# Server_DDR3L.net
KiCad netlist of a schematic drawn in Altium Designer
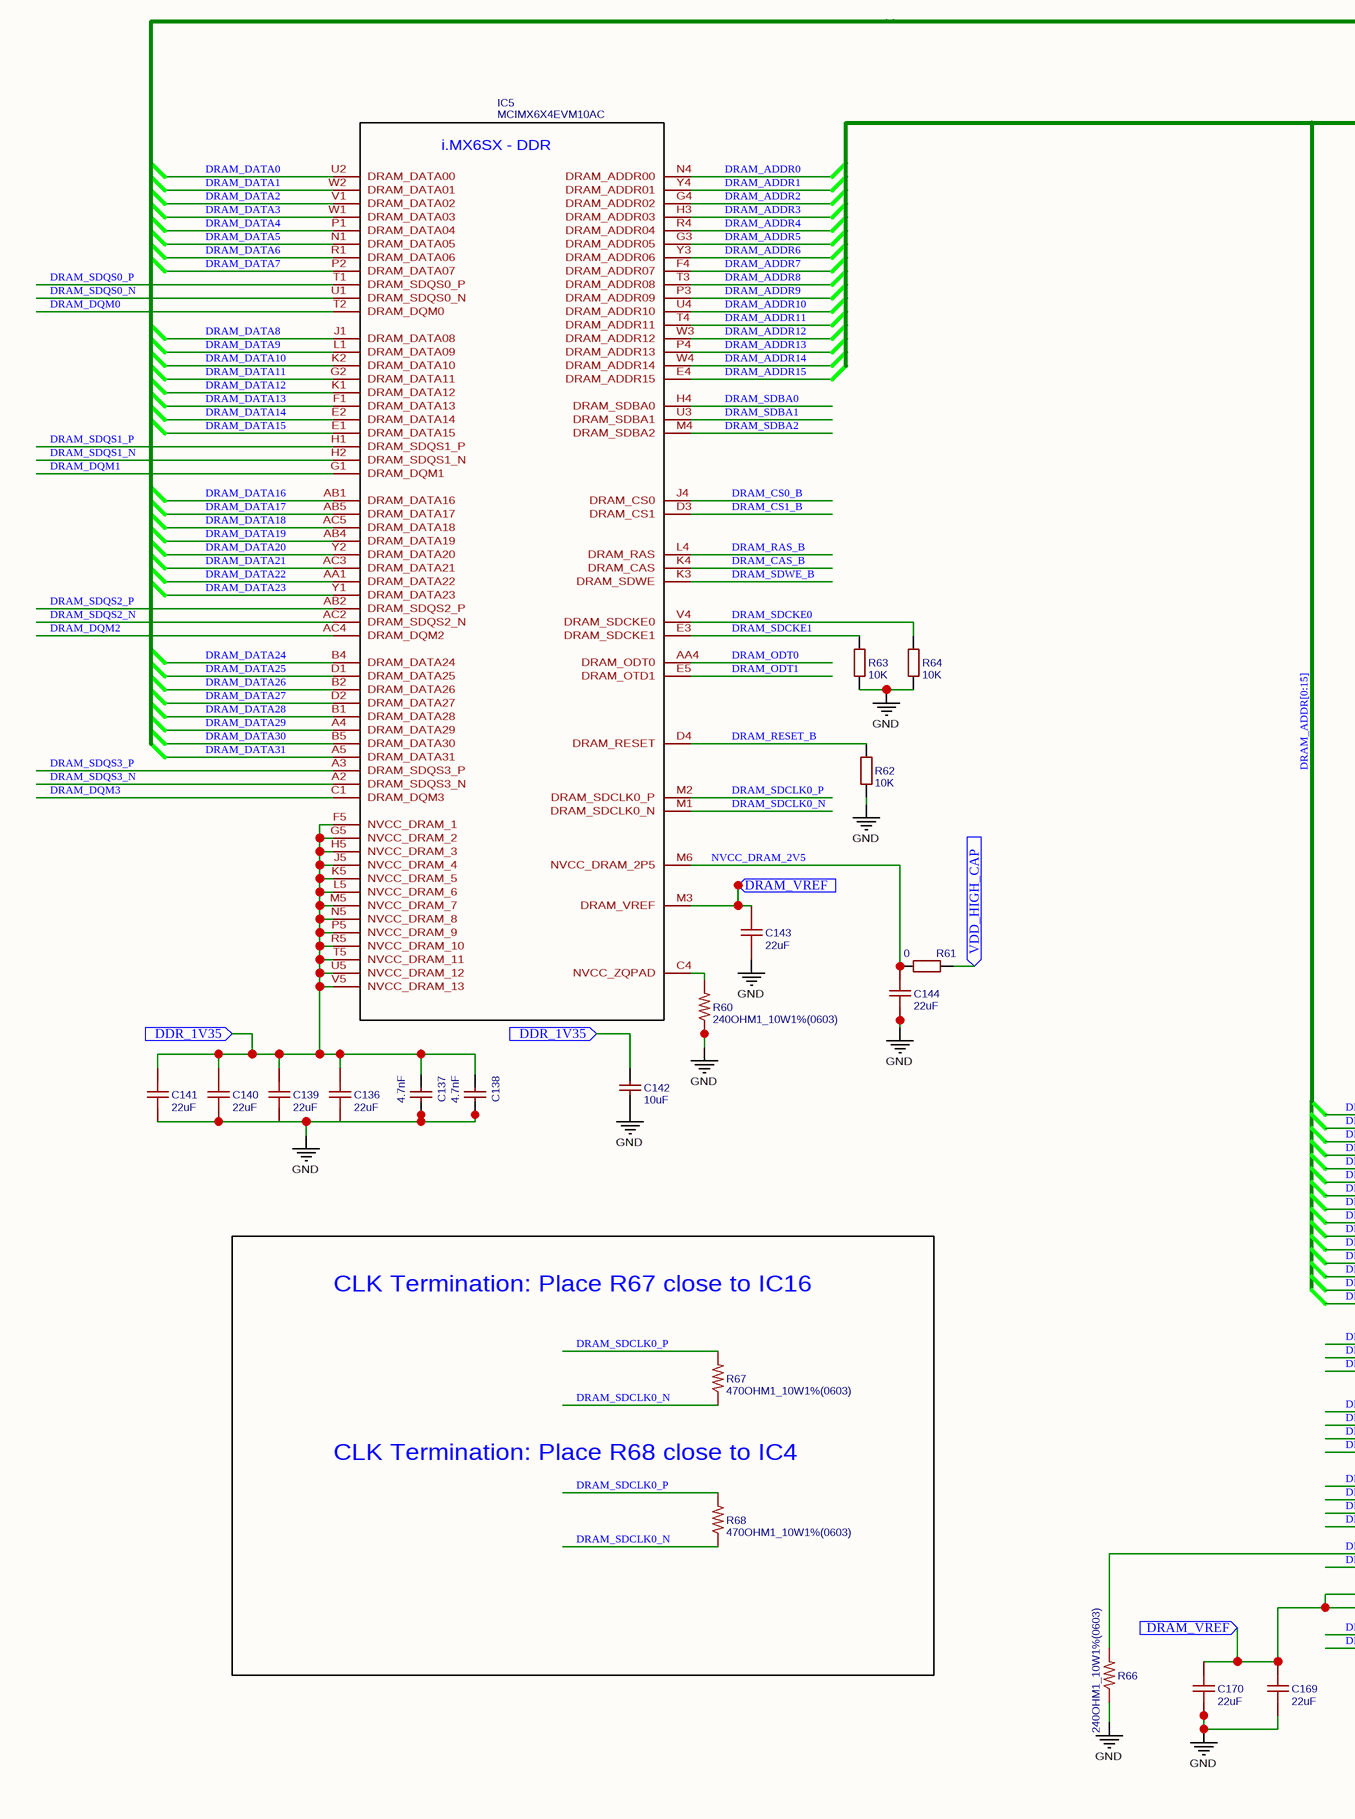
[diagram p0: Server DDR3L.schdoc, left]
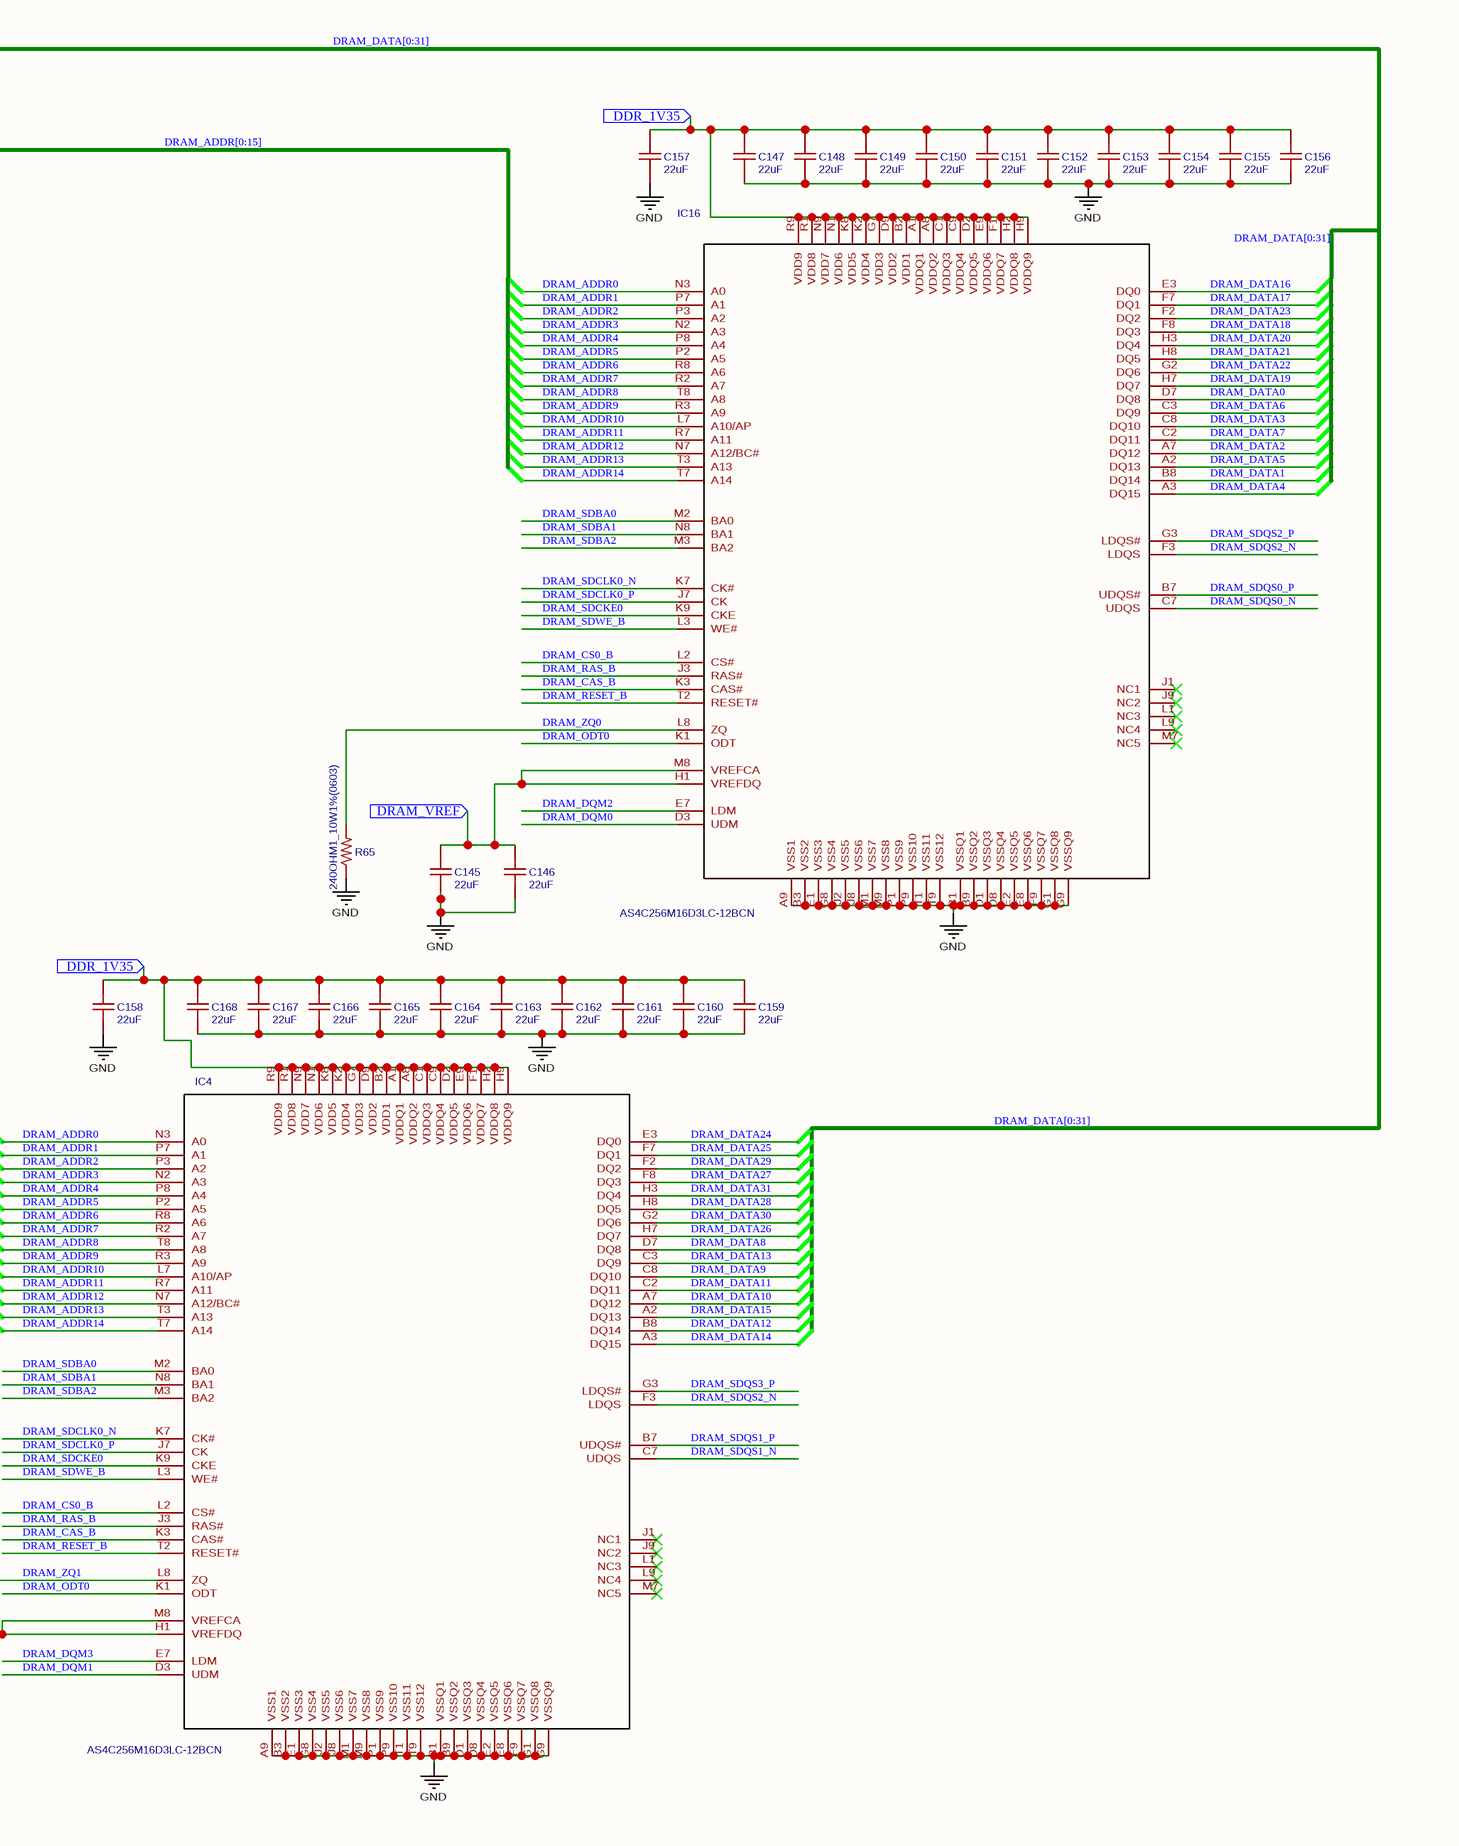
[diagram p1: Server DDR3L.schdoc, right]

(export (version "E")
  (design (tool "Eeschema 10.0.6"))
  (components
    (comp (ref "C136")
      (value "22uF")
      (fields
        (field (name "BOM_MANUFACTURER PART") "CL10A226MP8NUNE")
        (field (name "BOM_SUPPLIER PART") "C86295")
      )
      (libsource (lib "altium-import") (part "root_1_22uF_"))
    )
    (comp (ref "C137")
      (value "4.7nF")
      (fields
        (field (name "BOM_MANUFACTURER PART") "0805B472K500NT")
        (field (name "BOM_SUPPLIER PART") "C1744")
      )
      (libsource (lib "altium-import") (part "root_1_4.7nF_"))
    )
    (comp (ref "C138")
      (value "4.7nF")
      (fields
        (field (name "BOM_MANUFACTURER PART") "0805B472K500NT")
        (field (name "BOM_SUPPLIER PART") "C1744")
      )
      (libsource (lib "altium-import") (part "root_1_4.7nF_"))
    )
    (comp (ref "C139")
      (value "22uF")
      (fields
        (field (name "BOM_MANUFACTURER PART") "CL10A226MP8NUNE")
        (field (name "BOM_SUPPLIER PART") "C86295")
      )
      (libsource (lib "altium-import") (part "root_1_22uF_"))
    )
    (comp (ref "C140")
      (value "22uF")
      (fields
        (field (name "BOM_MANUFACTURER PART") "CL10A226MP8NUNE")
        (field (name "BOM_SUPPLIER PART") "C86295")
      )
      (libsource (lib "altium-import") (part "root_1_22uF_"))
    )
    (comp (ref "C141")
      (value "22uF")
      (fields
        (field (name "BOM_MANUFACTURER PART") "CL10A226MP8NUNE")
        (field (name "BOM_SUPPLIER PART") "C86295")
      )
      (libsource (lib "altium-import") (part "root_1_22uF_"))
    )
    (comp (ref "C142")
      (value "10uF")
      (fields
        (field (name "BOM_MANUFACTURER PART") "CL05A106MQ5NUNC")
        (field (name "BOM_SUPPLIER PART") "C15525")
      )
      (libsource (lib "altium-import") (part "root_1_10uF_"))
    )
    (comp (ref "C143")
      (value "22uF")
      (fields
        (field (name "BOM_MANUFACTURER PART") "CL10A226MP8NUNE")
        (field (name "BOM_SUPPLIER PART") "C86295")
      )
      (libsource (lib "altium-import") (part "root_1_22uF_"))
    )
    (comp (ref "C144")
      (value "22uF")
      (fields
        (field (name "BOM_MANUFACTURER PART") "CL10A226MP8NUNE")
        (field (name "BOM_SUPPLIER PART") "C86295")
      )
      (libsource (lib "altium-import") (part "root_1_22uF_"))
    )
    (comp (ref "C145")
      (value "22uF")
      (fields
        (field (name "BOM_MANUFACTURER PART") "CL10A226MP8NUNE")
        (field (name "BOM_SUPPLIER PART") "C86295")
      )
      (libsource (lib "altium-import") (part "root_1_22uF_"))
    )
    (comp (ref "C146")
      (value "22uF")
      (fields
        (field (name "BOM_MANUFACTURER PART") "CL10A226MP8NUNE")
        (field (name "BOM_SUPPLIER PART") "C86295")
      )
      (libsource (lib "altium-import") (part "root_1_22uF_"))
    )
    (comp (ref "C147")
      (value "22uF")
      (fields
        (field (name "BOM_MANUFACTURER PART") "CL10A226MP8NUNE")
        (field (name "BOM_SUPPLIER PART") "C86295")
      )
      (libsource (lib "altium-import") (part "root_1_22uF_"))
    )
    (comp (ref "C148")
      (value "22uF")
      (fields
        (field (name "BOM_MANUFACTURER PART") "CL10A226MP8NUNE")
        (field (name "BOM_SUPPLIER PART") "C86295")
      )
      (libsource (lib "altium-import") (part "root_1_22uF_"))
    )
    (comp (ref "C149")
      (value "22uF")
      (fields
        (field (name "BOM_MANUFACTURER PART") "CL10A226MP8NUNE")
        (field (name "BOM_SUPPLIER PART") "C86295")
      )
      (libsource (lib "altium-import") (part "root_1_22uF_"))
    )
    (comp (ref "C150")
      (value "22uF")
      (fields
        (field (name "BOM_MANUFACTURER PART") "CL10A226MP8NUNE")
        (field (name "BOM_SUPPLIER PART") "C86295")
      )
      (libsource (lib "altium-import") (part "root_1_22uF_"))
    )
    (comp (ref "C151")
      (value "22uF")
      (fields
        (field (name "BOM_MANUFACTURER PART") "CL10A226MP8NUNE")
        (field (name "BOM_SUPPLIER PART") "C86295")
      )
      (libsource (lib "altium-import") (part "root_1_22uF_"))
    )
    (comp (ref "C152")
      (value "22uF")
      (fields
        (field (name "BOM_MANUFACTURER PART") "CL10A226MP8NUNE")
        (field (name "BOM_SUPPLIER PART") "C86295")
      )
      (libsource (lib "altium-import") (part "root_1_22uF_"))
    )
    (comp (ref "C153")
      (value "22uF")
      (fields
        (field (name "BOM_MANUFACTURER PART") "CL10A226MP8NUNE")
        (field (name "BOM_SUPPLIER PART") "C86295")
      )
      (libsource (lib "altium-import") (part "root_1_22uF_"))
    )
    (comp (ref "C154")
      (value "22uF")
      (fields
        (field (name "BOM_MANUFACTURER PART") "CL10A226MP8NUNE")
        (field (name "BOM_SUPPLIER PART") "C86295")
      )
      (libsource (lib "altium-import") (part "root_1_22uF_"))
    )
    (comp (ref "C155")
      (value "22uF")
      (fields
        (field (name "BOM_MANUFACTURER PART") "CL10A226MP8NUNE")
        (field (name "BOM_SUPPLIER PART") "C86295")
      )
      (libsource (lib "altium-import") (part "root_1_22uF_"))
    )
    (comp (ref "C156")
      (value "22uF")
      (fields
        (field (name "BOM_MANUFACTURER PART") "CL10A226MP8NUNE")
        (field (name "BOM_SUPPLIER PART") "C86295")
      )
      (libsource (lib "altium-import") (part "root_1_22uF_"))
    )
    (comp (ref "C157")
      (value "22uF")
      (fields
        (field (name "BOM_MANUFACTURER PART") "CL10A226MP8NUNE")
        (field (name "BOM_SUPPLIER PART") "C86295")
      )
      (libsource (lib "altium-import") (part "root_1_22uF_"))
    )
    (comp (ref "C158")
      (value "22uF")
      (fields
        (field (name "BOM_MANUFACTURER PART") "CL10A226MP8NUNE")
        (field (name "BOM_SUPPLIER PART") "C86295")
      )
      (libsource (lib "altium-import") (part "root_1_22uF_"))
    )
    (comp (ref "C159")
      (value "22uF")
      (fields
        (field (name "BOM_MANUFACTURER PART") "CL10A226MP8NUNE")
        (field (name "BOM_SUPPLIER PART") "C86295")
      )
      (libsource (lib "altium-import") (part "root_1_22uF_"))
    )
    (comp (ref "C160")
      (value "22uF")
      (fields
        (field (name "BOM_MANUFACTURER PART") "CL10A226MP8NUNE")
        (field (name "BOM_SUPPLIER PART") "C86295")
      )
      (libsource (lib "altium-import") (part "root_1_22uF_"))
    )
    (comp (ref "C161")
      (value "22uF")
      (fields
        (field (name "BOM_MANUFACTURER PART") "CL10A226MP8NUNE")
        (field (name "BOM_SUPPLIER PART") "C86295")
      )
      (libsource (lib "altium-import") (part "root_1_22uF_"))
    )
    (comp (ref "C162")
      (value "22uF")
      (fields
        (field (name "BOM_MANUFACTURER PART") "CL10A226MP8NUNE")
        (field (name "BOM_SUPPLIER PART") "C86295")
      )
      (libsource (lib "altium-import") (part "root_1_22uF_"))
    )
    (comp (ref "C163")
      (value "22uF")
      (fields
        (field (name "BOM_MANUFACTURER PART") "CL10A226MP8NUNE")
        (field (name "BOM_SUPPLIER PART") "C86295")
      )
      (libsource (lib "altium-import") (part "root_1_22uF_"))
    )
    (comp (ref "C164")
      (value "22uF")
      (fields
        (field (name "BOM_MANUFACTURER PART") "CL10A226MP8NUNE")
        (field (name "BOM_SUPPLIER PART") "C86295")
      )
      (libsource (lib "altium-import") (part "root_1_22uF_"))
    )
    (comp (ref "C165")
      (value "22uF")
      (fields
        (field (name "BOM_MANUFACTURER PART") "CL10A226MP8NUNE")
        (field (name "BOM_SUPPLIER PART") "C86295")
      )
      (libsource (lib "altium-import") (part "root_1_22uF_"))
    )
    (comp (ref "C166")
      (value "22uF")
      (fields
        (field (name "BOM_MANUFACTURER PART") "CL10A226MP8NUNE")
        (field (name "BOM_SUPPLIER PART") "C86295")
      )
      (libsource (lib "altium-import") (part "root_1_22uF_"))
    )
    (comp (ref "C167")
      (value "22uF")
      (fields
        (field (name "BOM_MANUFACTURER PART") "CL10A226MP8NUNE")
        (field (name "BOM_SUPPLIER PART") "C86295")
      )
      (libsource (lib "altium-import") (part "root_1_22uF_"))
    )
    (comp (ref "C168")
      (value "22uF")
      (fields
        (field (name "BOM_MANUFACTURER PART") "CL10A226MP8NUNE")
        (field (name "BOM_SUPPLIER PART") "C86295")
      )
      (libsource (lib "altium-import") (part "root_1_22uF_"))
    )
    (comp (ref "C169")
      (value "22uF")
      (fields
        (field (name "BOM_MANUFACTURER PART") "CL10A226MP8NUNE")
        (field (name "BOM_SUPPLIER PART") "C86295")
      )
      (libsource (lib "altium-import") (part "root_1_22uF_"))
    )
    (comp (ref "C170")
      (value "22uF")
      (fields
        (field (name "BOM_MANUFACTURER PART") "CL10A226MP8NUNE")
        (field (name "BOM_SUPPLIER PART") "C86295")
      )
      (libsource (lib "altium-import") (part "root_1_22uF_"))
    )
    (comp (ref "IC4")
      (value "AS4C256M16D3LC-12BCN")
      (fields (field (name "CONTRIBUTOR") "Ke'Ondrae_Mell"))
      (libsource (lib "altium-import") (part "root_0_AS4C256M16D3LC-12BCN_"))
    )
    (comp (ref "IC5")
      (value "MCIMX6X4EVM10AC")
      (fields (field (name "SUBPART_NO") "1") (field (name "CONTRIBUTOR") "Ke'Ondrae_Mell"))
      (libsource (lib "altium-import") (part "root_0_MCIMX6X4EVM10AC_"))
    )
    (comp (ref "IC16")
      (value "AS4C256M16D3LC-12BCN")
      (fields (field (name "CONTRIBUTOR") "Ke'Ondrae_Mell"))
      (libsource (lib "altium-import") (part "root_0_AS4C256M16D3LC-12BCN_"))
    )
    (comp (ref "R60")
      (value "240OHM1_10W1%(0603)")
      (description "RES-07849")
      (fields (field (name "CONTRIBUTOR") "SparkFun"))
      (libsource (lib "altium-import") (part "root_1_240OHM1_10W1%(0603)_"))
    )
    (comp (ref "R61")
      (value "0")
      (fields
        (field (name "BOM_MANUFACTURER PART") "RK73Z1ETTP")
        (field (name "BOM_SUPPLIER PART") "C131359")
      )
      (libsource (lib "altium-import") (part "root_0_0_"))
    )
    (comp (ref "R62")
      (value "10K")
      (fields
        (field (name "BOM_MANUFACTURER PART") "0805W8F1002T5E")
        (field (name "BOM_SUPPLIER PART") "C17414")
      )
      (libsource (lib "altium-import") (part "root_3_10K_"))
    )
    (comp (ref "R63")
      (value "10K")
      (fields
        (field (name "BOM_MANUFACTURER PART") "0805W8F1002T5E")
        (field (name "BOM_SUPPLIER PART") "C17414")
      )
      (libsource (lib "altium-import") (part "root_3_10K_"))
    )
    (comp (ref "R64")
      (value "10K")
      (fields
        (field (name "BOM_MANUFACTURER PART") "0805W8F1002T5E")
        (field (name "BOM_SUPPLIER PART") "C17414")
      )
      (libsource (lib "altium-import") (part "root_3_10K_"))
    )
    (comp (ref "R65")
      (value "240OHM1_10W1%(0603)")
      (description "RES-07849")
      (fields (field (name "CONTRIBUTOR") "SparkFun"))
      (libsource (lib "altium-import") (part "root_1_240OHM1_10W1%(0603)_"))
    )
    (comp (ref "R66")
      (value "240OHM1_10W1%(0603)")
      (description "RES-07849")
      (fields (field (name "CONTRIBUTOR") "SparkFun"))
      (libsource (lib "altium-import") (part "root_1_240OHM1_10W1%(0603)_"))
    )
    (comp (ref "R67")
      (value "470OHM1_10W1%(0603)")
      (description "RES-07869")
      (fields (field (name "CONTRIBUTOR") "SparkFun"))
      (libsource (lib "altium-import") (part "root_1_470OHM1_10W1%(0603)_"))
    )
    (comp (ref "R68")
      (value "470OHM1_10W1%(0603)")
      (description "RES-07869")
      (fields (field (name "CONTRIBUTOR") "SparkFun"))
      (libsource (lib "altium-import") (part "root_1_470OHM1_10W1%(0603)_"))
    )
  )
  (nets
    (net (code "3") (name "/DDR_1V35") (class "Default")
      (node (ref "C136") (pin "2") (pinfunction "2_2") (pintype "passive"))
      (node (ref "C137") (pin "2") (pinfunction "2_2") (pintype "passive"))
      (node (ref "C138") (pin "2") (pinfunction "2_2") (pintype "passive"))
      (node (ref "C139") (pin "2") (pinfunction "2_2") (pintype "passive"))
      (node (ref "C140") (pin "2") (pinfunction "2_2") (pintype "passive"))
      (node (ref "C141") (pin "2") (pinfunction "2_2") (pintype "passive"))
      (node (ref "C142") (pin "2") (pinfunction "2_2") (pintype "passive"))
      (node (ref "C147") (pin "2") (pinfunction "2_2") (pintype "passive"))
      (node (ref "C148") (pin "2") (pinfunction "2_2") (pintype "passive"))
      (node (ref "C149") (pin "2") (pinfunction "2_2") (pintype "passive"))
      (node (ref "C150") (pin "2") (pinfunction "2_2") (pintype "passive"))
      (node (ref "C151") (pin "2") (pinfunction "2_2") (pintype "passive"))
      (node (ref "C152") (pin "2") (pinfunction "2_2") (pintype "passive"))
      (node (ref "C153") (pin "2") (pinfunction "2_2") (pintype "passive"))
      (node (ref "C154") (pin "2") (pinfunction "2_2") (pintype "passive"))
      (node (ref "C155") (pin "2") (pinfunction "2_2") (pintype "passive"))
      (node (ref "C156") (pin "2") (pinfunction "2_2") (pintype "passive"))
      (node (ref "C157") (pin "2") (pinfunction "2_2") (pintype "passive"))
      (node (ref "C158") (pin "2") (pinfunction "2_2") (pintype "passive"))
      (node (ref "C159") (pin "2") (pinfunction "2_2") (pintype "passive"))
      (node (ref "C160") (pin "2") (pinfunction "2_2") (pintype "passive"))
      (node (ref "C161") (pin "2") (pinfunction "2_2") (pintype "passive"))
      (node (ref "C162") (pin "2") (pinfunction "2_2") (pintype "passive"))
      (node (ref "C163") (pin "2") (pinfunction "2_2") (pintype "passive"))
      (node (ref "C164") (pin "2") (pinfunction "2_2") (pintype "passive"))
      (node (ref "C165") (pin "2") (pinfunction "2_2") (pintype "passive"))
      (node (ref "C166") (pin "2") (pinfunction "2_2") (pintype "passive"))
      (node (ref "C167") (pin "2") (pinfunction "2_2") (pintype "passive"))
      (node (ref "C168") (pin "2") (pinfunction "2_2") (pintype "passive"))
      (node (ref "IC16") (pin "A1") (pinfunction "VDDQ1_A1") (pintype "passive"))
      (node (ref "IC16") (pin "A8") (pinfunction "VDDQ2_A8") (pintype "passive"))
      (node (ref "IC16") (pin "B2") (pinfunction "VDD1_B2") (pintype "passive"))
      (node (ref "IC16") (pin "C1") (pinfunction "VDDQ3_C1") (pintype "passive"))
      (node (ref "IC16") (pin "C9") (pinfunction "VDDQ4_C9") (pintype "passive"))
      (node (ref "IC16") (pin "D2") (pinfunction "VDDQ5_D2") (pintype "passive"))
      (node (ref "IC16") (pin "D9") (pinfunction "VDD2_D9") (pintype "passive"))
      (node (ref "IC16") (pin "E9") (pinfunction "VDDQ6_E9") (pintype "passive"))
      (node (ref "IC16") (pin "F1") (pinfunction "VDDQ7_F1") (pintype "passive"))
      (node (ref "IC16") (pin "G7") (pinfunction "VDD3_G7") (pintype "passive"))
      (node (ref "IC16") (pin "H2") (pinfunction "VDDQ8_H2") (pintype "passive"))
      (node (ref "IC16") (pin "H9") (pinfunction "VDDQ9_H9") (pintype "passive"))
      (node (ref "IC16") (pin "K2") (pinfunction "VDD4_K2") (pintype "passive"))
      (node (ref "IC16") (pin "K8") (pinfunction "VDD5_K8") (pintype "passive"))
      (node (ref "IC16") (pin "N1") (pinfunction "VDD6_N1") (pintype "passive"))
      (node (ref "IC16") (pin "N9") (pinfunction "VDD7_N9") (pintype "passive"))
      (node (ref "IC16") (pin "R1") (pinfunction "VDD8_R1") (pintype "passive"))
      (node (ref "IC16") (pin "R9") (pinfunction "VDD9_R9") (pintype "passive"))
      (node (ref "IC4") (pin "A1") (pinfunction "VDDQ1_A1") (pintype "passive"))
      (node (ref "IC4") (pin "A8") (pinfunction "VDDQ2_A8") (pintype "passive"))
      (node (ref "IC4") (pin "B2") (pinfunction "VDD1_B2") (pintype "passive"))
      (node (ref "IC4") (pin "C1") (pinfunction "VDDQ3_C1") (pintype "passive"))
      (node (ref "IC4") (pin "C9") (pinfunction "VDDQ4_C9") (pintype "passive"))
      (node (ref "IC4") (pin "D2") (pinfunction "VDDQ5_D2") (pintype "passive"))
      (node (ref "IC4") (pin "D9") (pinfunction "VDD2_D9") (pintype "passive"))
      (node (ref "IC4") (pin "E9") (pinfunction "VDDQ6_E9") (pintype "passive"))
      (node (ref "IC4") (pin "F1") (pinfunction "VDDQ7_F1") (pintype "passive"))
      (node (ref "IC4") (pin "G7") (pinfunction "VDD3_G7") (pintype "passive"))
      (node (ref "IC4") (pin "H2") (pinfunction "VDDQ8_H2") (pintype "passive"))
      (node (ref "IC4") (pin "H9") (pinfunction "VDDQ9_H9") (pintype "passive"))
      (node (ref "IC4") (pin "K2") (pinfunction "VDD4_K2") (pintype "passive"))
      (node (ref "IC4") (pin "K8") (pinfunction "VDD5_K8") (pintype "passive"))
      (node (ref "IC4") (pin "N1") (pinfunction "VDD6_N1") (pintype "passive"))
      (node (ref "IC4") (pin "N9") (pinfunction "VDD7_N9") (pintype "passive"))
      (node (ref "IC4") (pin "R1") (pinfunction "VDD8_R1") (pintype "passive"))
      (node (ref "IC4") (pin "R9") (pinfunction "VDD9_R9") (pintype "passive"))
      (node (ref "IC5") (pin "F5") (pinfunction "NVCC_DRAM_1_F5") (pintype "passive"))
      (node (ref "IC5") (pin "G5") (pinfunction "NVCC_DRAM_2_G5") (pintype "passive"))
      (node (ref "IC5") (pin "H5") (pinfunction "NVCC_DRAM_3_H5") (pintype "passive"))
      (node (ref "IC5") (pin "J5") (pinfunction "NVCC_DRAM_4_J5") (pintype "passive"))
      (node (ref "IC5") (pin "K5") (pinfunction "NVCC_DRAM_5_K5") (pintype "passive"))
      (node (ref "IC5") (pin "L5") (pinfunction "NVCC_DRAM_6_L5") (pintype "passive"))
      (node (ref "IC5") (pin "M5") (pinfunction "NVCC_DRAM_7_M5") (pintype "passive"))
      (node (ref "IC5") (pin "N5") (pinfunction "NVCC_DRAM_8_N5") (pintype "passive"))
      (node (ref "IC5") (pin "P5") (pinfunction "NVCC_DRAM_9_P5") (pintype "passive"))
      (node (ref "IC5") (pin "R5") (pinfunction "NVCC_DRAM_10_R5") (pintype "passive"))
      (node (ref "IC5") (pin "T5") (pinfunction "NVCC_DRAM_11_T5") (pintype "passive"))
      (node (ref "IC5") (pin "U5") (pinfunction "NVCC_DRAM_12_U5") (pintype "passive"))
      (node (ref "IC5") (pin "V5") (pinfunction "NVCC_DRAM_13_V5") (pintype "passive"))
    )
    (net (code "4") (name "/DRAM_ADDR0") (class "Default")
      (node (ref "IC16") (pin "N3") (pinfunction "A0_N3") (pintype "passive"))
      (node (ref "IC4") (pin "N3") (pinfunction "A0_N3") (pintype "passive"))
      (node (ref "IC5") (pin "N4") (pinfunction "DRAM_ADDR00_N4") (pintype "passive"))
    )
    (net (code "5") (name "/DRAM_ADDR1") (class "Default")
      (node (ref "IC16") (pin "P7") (pinfunction "A1_P7") (pintype "passive"))
      (node (ref "IC4") (pin "P7") (pinfunction "A1_P7") (pintype "passive"))
      (node (ref "IC5") (pin "Y4") (pinfunction "DRAM_ADDR01_Y4") (pintype "passive"))
    )
    (net (code "6") (name "/DRAM_ADDR2") (class "Default")
      (node (ref "IC16") (pin "P3") (pinfunction "A2_P3") (pintype "passive"))
      (node (ref "IC4") (pin "P3") (pinfunction "A2_P3") (pintype "passive"))
      (node (ref "IC5") (pin "G4") (pinfunction "DRAM_ADDR02_G4") (pintype "passive"))
    )
    (net (code "7") (name "/DRAM_ADDR3") (class "Default")
      (node (ref "IC16") (pin "N2") (pinfunction "A3_N2") (pintype "passive"))
      (node (ref "IC4") (pin "N2") (pinfunction "A3_N2") (pintype "passive"))
      (node (ref "IC5") (pin "H3") (pinfunction "DRAM_ADDR03_H3") (pintype "passive"))
    )
    (net (code "8") (name "/DRAM_ADDR4") (class "Default")
      (node (ref "IC16") (pin "P8") (pinfunction "A4_P8") (pintype "passive"))
      (node (ref "IC4") (pin "P8") (pinfunction "A4_P8") (pintype "passive"))
      (node (ref "IC5") (pin "R4") (pinfunction "DRAM_ADDR04_R4") (pintype "passive"))
    )
    (net (code "9") (name "/DRAM_ADDR5") (class "Default")
      (node (ref "IC16") (pin "P2") (pinfunction "A5_P2") (pintype "passive"))
      (node (ref "IC4") (pin "P2") (pinfunction "A5_P2") (pintype "passive"))
      (node (ref "IC5") (pin "G3") (pinfunction "DRAM_ADDR05_G3") (pintype "passive"))
    )
    (net (code "10") (name "/DRAM_ADDR6") (class "Default")
      (node (ref "IC16") (pin "R8") (pinfunction "A6_R8") (pintype "passive"))
      (node (ref "IC4") (pin "R8") (pinfunction "A6_R8") (pintype "passive"))
      (node (ref "IC5") (pin "Y3") (pinfunction "DRAM_ADDR06_Y3") (pintype "passive"))
    )
    (net (code "11") (name "/DRAM_ADDR7") (class "Default")
      (node (ref "IC16") (pin "R2") (pinfunction "A7_R2") (pintype "passive"))
      (node (ref "IC4") (pin "R2") (pinfunction "A7_R2") (pintype "passive"))
      (node (ref "IC5") (pin "F4") (pinfunction "DRAM_ADDR07_F4") (pintype "passive"))
    )
    (net (code "12") (name "/DRAM_ADDR8") (class "Default")
      (node (ref "IC16") (pin "T8") (pinfunction "A8_T8") (pintype "passive"))
      (node (ref "IC4") (pin "T8") (pinfunction "A8_T8") (pintype "passive"))
      (node (ref "IC5") (pin "T3") (pinfunction "DRAM_ADDR08_T3") (pintype "passive"))
    )
    (net (code "13") (name "/DRAM_ADDR9") (class "Default")
      (node (ref "IC16") (pin "R3") (pinfunction "A9_R3") (pintype "passive"))
      (node (ref "IC4") (pin "R3") (pinfunction "A9_R3") (pintype "passive"))
      (node (ref "IC5") (pin "P3") (pinfunction "DRAM_ADDR09_P3") (pintype "passive"))
    )
    (net (code "14") (name "/DRAM_ADDR10") (class "Default")
      (node (ref "IC16") (pin "L7") (pinfunction "A10/AP_L7") (pintype "passive"))
      (node (ref "IC4") (pin "L7") (pinfunction "A10/AP_L7") (pintype "passive"))
      (node (ref "IC5") (pin "U4") (pinfunction "DRAM_ADDR10_U4") (pintype "passive"))
    )
    (net (code "15") (name "/DRAM_ADDR11") (class "Default")
      (node (ref "IC16") (pin "R7") (pinfunction "A11_R7") (pintype "passive"))
      (node (ref "IC4") (pin "R7") (pinfunction "A11_R7") (pintype "passive"))
      (node (ref "IC5") (pin "T4") (pinfunction "DRAM_ADDR11_T4") (pintype "passive"))
    )
    (net (code "16") (name "/DRAM_ADDR12") (class "Default")
      (node (ref "IC16") (pin "N7") (pinfunction "A12/BC#_N7") (pintype "passive"))
      (node (ref "IC4") (pin "N7") (pinfunction "A12/BC#_N7") (pintype "passive"))
      (node (ref "IC5") (pin "W3") (pinfunction "DRAM_ADDR12_W3") (pintype "passive"))
    )
    (net (code "17") (name "/DRAM_ADDR13") (class "Default")
      (node (ref "IC16") (pin "T3") (pinfunction "A13_T3") (pintype "passive"))
      (node (ref "IC4") (pin "T3") (pinfunction "A13_T3") (pintype "passive"))
      (node (ref "IC5") (pin "P4") (pinfunction "DRAM_ADDR13_P4") (pintype "passive"))
    )
    (net (code "18") (name "/DRAM_ADDR14") (class "Default")
      (node (ref "IC16") (pin "T7") (pinfunction "A14_T7") (pintype "passive"))
      (node (ref "IC4") (pin "T7") (pinfunction "A14_T7") (pintype "passive"))
      (node (ref "IC5") (pin "W4") (pinfunction "DRAM_ADDR14_W4") (pintype "passive"))
    )
    (net (code "19") (name "/DRAM_ADDR15") (class "Default")
      (node (ref "IC5") (pin "E4") (pinfunction "DRAM_ADDR15_E4") (pintype "passive"))
    )
    (net (code "20") (name "/DRAM_CAS_B") (class "Default")
      (node (ref "IC16") (pin "K3") (pinfunction "CAS#_K3") (pintype "passive"))
      (node (ref "IC4") (pin "K3") (pinfunction "CAS#_K3") (pintype "passive"))
      (node (ref "IC5") (pin "K4") (pinfunction "DRAM_CAS_K4") (pintype "passive"))
    )
    (net (code "21") (name "/DRAM_CS0_B") (class "Default")
      (node (ref "IC16") (pin "L2") (pinfunction "CS#_L2") (pintype "passive"))
      (node (ref "IC4") (pin "L2") (pinfunction "CS#_L2") (pintype "passive"))
      (node (ref "IC5") (pin "J4") (pinfunction "DRAM_CS0_J4") (pintype "passive"))
    )
    (net (code "22") (name "/DRAM_CS1_B") (class "Default")
      (node (ref "IC5") (pin "D3") (pinfunction "DRAM_CS1_D3") (pintype "passive"))
    )
    (net (code "23") (name "/DRAM_DATA0") (class "Default")
      (node (ref "IC16") (pin "D7") (pinfunction "DQ8_D7") (pintype "passive"))
      (node (ref "IC5") (pin "U2") (pinfunction "DRAM_DATA00_U2") (pintype "passive"))
    )
    (net (code "24") (name "/DRAM_DATA1") (class "Default")
      (node (ref "IC16") (pin "B8") (pinfunction "DQ14_B8") (pintype "passive"))
      (node (ref "IC5") (pin "W2") (pinfunction "DRAM_DATA01_W2") (pintype "passive"))
    )
    (net (code "25") (name "/DRAM_DATA2") (class "Default")
      (node (ref "IC16") (pin "A7") (pinfunction "DQ12_A7") (pintype "passive"))
      (node (ref "IC5") (pin "V1") (pinfunction "DRAM_DATA02_V1") (pintype "passive"))
    )
    (net (code "26") (name "/DRAM_DATA3") (class "Default")
      (node (ref "IC16") (pin "C8") (pinfunction "DQ10_C8") (pintype "passive"))
      (node (ref "IC5") (pin "W1") (pinfunction "DRAM_DATA03_W1") (pintype "passive"))
    )
    (net (code "27") (name "/DRAM_DATA4") (class "Default")
      (node (ref "IC16") (pin "A3") (pinfunction "DQ15_A3") (pintype "passive"))
      (node (ref "IC5") (pin "P1") (pinfunction "DRAM_DATA04_P1") (pintype "passive"))
    )
    (net (code "28") (name "/DRAM_DATA5") (class "Default")
      (node (ref "IC16") (pin "A2") (pinfunction "DQ13_A2") (pintype "passive"))
      (node (ref "IC5") (pin "N1") (pinfunction "DRAM_DATA05_N1") (pintype "passive"))
    )
    (net (code "29") (name "/DRAM_DATA6") (class "Default")
      (node (ref "IC16") (pin "C3") (pinfunction "DQ9_C3") (pintype "passive"))
      (node (ref "IC5") (pin "R1") (pinfunction "DRAM_DATA06_R1") (pintype "passive"))
    )
    (net (code "30") (name "/DRAM_DATA7") (class "Default")
      (node (ref "IC16") (pin "C2") (pinfunction "DQ11_C2") (pintype "passive"))
      (node (ref "IC5") (pin "P2") (pinfunction "DRAM_DATA07_P2") (pintype "passive"))
    )
    (net (code "31") (name "/DRAM_DATA8") (class "Default")
      (node (ref "IC4") (pin "D7") (pinfunction "DQ8_D7") (pintype "passive"))
      (node (ref "IC5") (pin "J1") (pinfunction "DRAM_DATA08_J1") (pintype "passive"))
    )
    (net (code "32") (name "/DRAM_DATA9") (class "Default")
      (node (ref "IC4") (pin "C8") (pinfunction "DQ10_C8") (pintype "passive"))
      (node (ref "IC5") (pin "L1") (pinfunction "DRAM_DATA09_L1") (pintype "passive"))
    )
    (net (code "33") (name "/DRAM_DATA10") (class "Default")
      (node (ref "IC4") (pin "A7") (pinfunction "DQ12_A7") (pintype "passive"))
      (node (ref "IC5") (pin "K2") (pinfunction "DRAM_DATA10_K2") (pintype "passive"))
    )
    (net (code "34") (name "/DRAM_DATA11") (class "Default")
      (node (ref "IC4") (pin "C2") (pinfunction "DQ11_C2") (pintype "passive"))
      (node (ref "IC5") (pin "G2") (pinfunction "DRAM_DATA11_G2") (pintype "passive"))
    )
    (net (code "35") (name "/DRAM_DATA12") (class "Default")
      (node (ref "IC4") (pin "B8") (pinfunction "DQ14_B8") (pintype "passive"))
      (node (ref "IC5") (pin "K1") (pinfunction "DRAM_DATA12_K1") (pintype "passive"))
    )
    (net (code "36") (name "/DRAM_DATA13") (class "Default")
      (node (ref "IC4") (pin "C3") (pinfunction "DQ9_C3") (pintype "passive"))
      (node (ref "IC5") (pin "F1") (pinfunction "DRAM_DATA13_F1") (pintype "passive"))
    )
    (net (code "37") (name "/DRAM_DATA14") (class "Default")
      (node (ref "IC4") (pin "A3") (pinfunction "DQ15_A3") (pintype "passive"))
      (node (ref "IC5") (pin "E2") (pinfunction "DRAM_DATA14_E2") (pintype "passive"))
    )
    (net (code "38") (name "/DRAM_DATA15") (class "Default")
      (node (ref "IC4") (pin "A2") (pinfunction "DQ13_A2") (pintype "passive"))
      (node (ref "IC5") (pin "E1") (pinfunction "DRAM_DATA15_E1") (pintype "passive"))
    )
    (net (code "39") (name "/DRAM_DATA16") (class "Default")
      (node (ref "IC16") (pin "E3") (pinfunction "DQ0_E3") (pintype "passive"))
      (node (ref "IC5") (pin "AB1") (pinfunction "DRAM_DATA16_AB1") (pintype "passive"))
    )
    (net (code "40") (name "/DRAM_DATA17") (class "Default")
      (node (ref "IC16") (pin "F7") (pinfunction "DQ1_F7") (pintype "passive"))
      (node (ref "IC5") (pin "AB5") (pinfunction "DRAM_DATA17_AB5") (pintype "passive"))
    )
    (net (code "41") (name "/DRAM_DATA18") (class "Default")
      (node (ref "IC16") (pin "F8") (pinfunction "DQ3_F8") (pintype "passive"))
      (node (ref "IC5") (pin "AC5") (pinfunction "DRAM_DATA18_AC5") (pintype "passive"))
    )
    (net (code "42") (name "/DRAM_DATA19") (class "Default")
      (node (ref "IC16") (pin "H7") (pinfunction "DQ7_H7") (pintype "passive"))
      (node (ref "IC5") (pin "AB4") (pinfunction "DRAM_DATA19_AB4") (pintype "passive"))
    )
    (net (code "43") (name "/DRAM_DATA20") (class "Default")
      (node (ref "IC16") (pin "H3") (pinfunction "DQ4_H3") (pintype "passive"))
      (node (ref "IC5") (pin "Y2") (pinfunction "DRAM_DATA20_Y2") (pintype "passive"))
    )
    (net (code "44") (name "/DRAM_DATA21") (class "Default")
      (node (ref "IC16") (pin "H8") (pinfunction "DQ5_H8") (pintype "passive"))
      (node (ref "IC5") (pin "AC3") (pinfunction "DRAM_DATA21_AC3") (pintype "passive"))
    )
    (net (code "45") (name "/DRAM_DATA22") (class "Default")
      (node (ref "IC16") (pin "G2") (pinfunction "DQ6_G2") (pintype "passive"))
      (node (ref "IC5") (pin "AA1") (pinfunction "DRAM_DATA22_AA1") (pintype "passive"))
    )
    (net (code "46") (name "/DRAM_DATA23") (class "Default")
      (node (ref "IC16") (pin "F2") (pinfunction "DQ2_F2") (pintype "passive"))
      (node (ref "IC5") (pin "Y1") (pinfunction "DRAM_DATA23_Y1") (pintype "passive"))
    )
    (net (code "47") (name "/DRAM_DATA24") (class "Default")
      (node (ref "IC4") (pin "E3") (pinfunction "DQ0_E3") (pintype "passive"))
      (node (ref "IC5") (pin "B4") (pinfunction "DRAM_DATA24_B4") (pintype "passive"))
    )
    (net (code "48") (name "/DRAM_DATA25") (class "Default")
      (node (ref "IC4") (pin "F7") (pinfunction "DQ1_F7") (pintype "passive"))
      (node (ref "IC5") (pin "D1") (pinfunction "DRAM_DATA25_D1") (pintype "passive"))
    )
    (net (code "49") (name "/DRAM_DATA26") (class "Default")
      (node (ref "IC4") (pin "H7") (pinfunction "DQ7_H7") (pintype "passive"))
      (node (ref "IC5") (pin "B2") (pinfunction "DRAM_DATA26_B2") (pintype "passive"))
    )
    (net (code "50") (name "/DRAM_DATA27") (class "Default")
      (node (ref "IC4") (pin "F8") (pinfunction "DQ3_F8") (pintype "passive"))
      (node (ref "IC5") (pin "D2") (pinfunction "DRAM_DATA27_D2") (pintype "passive"))
    )
    (net (code "51") (name "/DRAM_DATA28") (class "Default")
      (node (ref "IC4") (pin "H8") (pinfunction "DQ5_H8") (pintype "passive"))
      (node (ref "IC5") (pin "B1") (pinfunction "DRAM_DATA28_B1") (pintype "passive"))
    )
    (net (code "52") (name "/DRAM_DATA29") (class "Default")
      (node (ref "IC4") (pin "F2") (pinfunction "DQ2_F2") (pintype "passive"))
      (node (ref "IC5") (pin "A4") (pinfunction "DRAM_DATA29_A4") (pintype "passive"))
    )
    (net (code "53") (name "/DRAM_DATA30") (class "Default")
      (node (ref "IC4") (pin "G2") (pinfunction "DQ6_G2") (pintype "passive"))
      (node (ref "IC5") (pin "B5") (pinfunction "DRAM_DATA30_B5") (pintype "passive"))
    )
    (net (code "54") (name "/DRAM_DATA31") (class "Default")
      (node (ref "IC4") (pin "H3") (pinfunction "DQ4_H3") (pintype "passive"))
      (node (ref "IC5") (pin "A5") (pinfunction "DRAM_DATA31_A5") (pintype "passive"))
    )
    (net (code "55") (name "/DRAM_DQM0") (class "Default")
      (node (ref "IC16") (pin "D3") (pinfunction "UDM_D3") (pintype "passive"))
      (node (ref "IC5") (pin "T2") (pinfunction "DRAM_DQM0_T2") (pintype "passive"))
    )
    (net (code "56") (name "/DRAM_DQM1") (class "Default")
      (node (ref "IC4") (pin "D3") (pinfunction "UDM_D3") (pintype "passive"))
      (node (ref "IC5") (pin "G1") (pinfunction "DRAM_DQM1_G1") (pintype "passive"))
    )
    (net (code "57") (name "/DRAM_DQM2") (class "Default")
      (node (ref "IC16") (pin "E7") (pinfunction "LDM_E7") (pintype "passive"))
      (node (ref "IC5") (pin "AC4") (pinfunction "DRAM_DQM2_AC4") (pintype "passive"))
    )
    (net (code "58") (name "/DRAM_DQM3") (class "Default")
      (node (ref "IC4") (pin "E7") (pinfunction "LDM_E7") (pintype "passive"))
      (node (ref "IC5") (pin "C1") (pinfunction "DRAM_DQM3_C1") (pintype "passive"))
    )
    (net (code "59") (name "/DRAM_ODT0") (class "Default")
      (node (ref "IC16") (pin "K1") (pinfunction "ODT_K1") (pintype "passive"))
      (node (ref "IC4") (pin "K1") (pinfunction "ODT_K1") (pintype "passive"))
      (node (ref "IC5") (pin "AA4") (pinfunction "DRAM_ODT0_AA4") (pintype "passive"))
    )
    (net (code "60") (name "/DRAM_ODT1") (class "Default")
      (node (ref "IC5") (pin "E5") (pinfunction "DRAM_OTD1_E5") (pintype "passive"))
    )
    (net (code "61") (name "/DRAM_RAS_B") (class "Default")
      (node (ref "IC16") (pin "J3") (pinfunction "RAS#_J3") (pintype "passive"))
      (node (ref "IC4") (pin "J3") (pinfunction "RAS#_J3") (pintype "passive"))
      (node (ref "IC5") (pin "L4") (pinfunction "DRAM_RAS_L4") (pintype "passive"))
    )
    (net (code "62") (name "/DRAM_RESET_B") (class "Default")
      (node (ref "IC16") (pin "T2") (pinfunction "RESET#_T2") (pintype "passive"))
      (node (ref "IC4") (pin "T2") (pinfunction "RESET#_T2") (pintype "passive"))
      (node (ref "IC5") (pin "D4") (pinfunction "DRAM_RESET_D4") (pintype "passive"))
      (node (ref "R62") (pin "1") (pinfunction "1_1") (pintype "passive"))
    )
    (net (code "63") (name "/DRAM_SDBA0") (class "Default")
      (node (ref "IC16") (pin "M2") (pinfunction "BA0_M2") (pintype "passive"))
      (node (ref "IC4") (pin "M2") (pinfunction "BA0_M2") (pintype "passive"))
      (node (ref "IC5") (pin "H4") (pinfunction "DRAM_SDBA0_H4") (pintype "passive"))
    )
    (net (code "64") (name "/DRAM_SDBA1") (class "Default")
      (node (ref "IC16") (pin "N8") (pinfunction "BA1_N8") (pintype "passive"))
      (node (ref "IC4") (pin "N8") (pinfunction "BA1_N8") (pintype "passive"))
      (node (ref "IC5") (pin "U3") (pinfunction "DRAM_SDBA1_U3") (pintype "passive"))
    )
    (net (code "65") (name "/DRAM_SDBA2") (class "Default")
      (node (ref "IC16") (pin "M3") (pinfunction "BA2_M3") (pintype "passive"))
      (node (ref "IC4") (pin "M3") (pinfunction "BA2_M3") (pintype "passive"))
      (node (ref "IC5") (pin "M4") (pinfunction "DRAM_SDBA2_M4") (pintype "passive"))
    )
    (net (code "66") (name "/DRAM_SDCKE0") (class "Default")
      (node (ref "IC16") (pin "K9") (pinfunction "CKE_K9") (pintype "passive"))
      (node (ref "IC4") (pin "K9") (pinfunction "CKE_K9") (pintype "passive"))
      (node (ref "IC5") (pin "V4") (pinfunction "DRAM_SDCKE0_V4") (pintype "passive"))
      (node (ref "R64") (pin "1") (pinfunction "1_1") (pintype "passive"))
    )
    (net (code "67") (name "/DRAM_SDCKE1") (class "Default")
      (node (ref "IC5") (pin "E3") (pinfunction "DRAM_SDCKE1_E3") (pintype "passive"))
      (node (ref "R63") (pin "1") (pinfunction "1_1") (pintype "passive"))
    )
    (net (code "68") (name "/DRAM_SDCLK0_N") (class "Default")
      (node (ref "IC16") (pin "K7") (pinfunction "CK#_K7") (pintype "passive"))
      (node (ref "IC4") (pin "K7") (pinfunction "CK#_K7") (pintype "passive"))
      (node (ref "IC5") (pin "M1") (pinfunction "DRAM_SDCLK0_N_M1") (pintype "passive"))
      (node (ref "R67") (pin "1") (pinfunction "1_1") (pintype "passive"))
      (node (ref "R68") (pin "1") (pinfunction "1_1") (pintype "passive"))
    )
    (net (code "69") (name "/DRAM_SDCLK0_P") (class "Default")
      (node (ref "IC16") (pin "J7") (pinfunction "CK_J7") (pintype "passive"))
      (node (ref "IC4") (pin "J7") (pinfunction "CK_J7") (pintype "passive"))
      (node (ref "IC5") (pin "M2") (pinfunction "DRAM_SDCLK0_P_M2") (pintype "passive"))
      (node (ref "R67") (pin "2") (pinfunction "2_2") (pintype "passive"))
      (node (ref "R68") (pin "2") (pinfunction "2_2") (pintype "passive"))
    )
    (net (code "70") (name "/DRAM_SDQS0_N") (class "Default")
      (node (ref "IC16") (pin "C7") (pinfunction "UDQS_C7") (pintype "passive"))
      (node (ref "IC5") (pin "U1") (pinfunction "DRAM_SDQS0_N_U1") (pintype "passive"))
    )
    (net (code "71") (name "/DRAM_SDQS0_P") (class "Default")
      (node (ref "IC16") (pin "B7") (pinfunction "UDQS#_B7") (pintype "passive"))
      (node (ref "IC5") (pin "T1") (pinfunction "DRAM_SDQS0_P_T1") (pintype "passive"))
    )
    (net (code "72") (name "/DRAM_SDQS1_N") (class "Default")
      (node (ref "IC4") (pin "C7") (pinfunction "UDQS_C7") (pintype "passive"))
      (node (ref "IC5") (pin "H2") (pinfunction "DRAM_SDQS1_N_H2") (pintype "passive"))
    )
    (net (code "73") (name "/DRAM_SDQS1_P") (class "Default")
      (node (ref "IC4") (pin "B7") (pinfunction "UDQS#_B7") (pintype "passive"))
      (node (ref "IC5") (pin "H1") (pinfunction "DRAM_SDQS1_P_H1") (pintype "passive"))
    )
    (net (code "74") (name "/DRAM_SDQS2_N") (class "Default")
      (node (ref "IC16") (pin "F3") (pinfunction "LDQS_F3") (pintype "passive"))
      (node (ref "IC4") (pin "F3") (pinfunction "LDQS_F3") (pintype "passive"))
      (node (ref "IC5") (pin "AC2") (pinfunction "DRAM_SDQS2_N_AC2") (pintype "passive"))
    )
    (net (code "75") (name "/DRAM_SDQS2_P") (class "Default")
      (node (ref "IC16") (pin "G3") (pinfunction "LDQS#_G3") (pintype "passive"))
      (node (ref "IC5") (pin "AB2") (pinfunction "DRAM_SDQS2_P_AB2") (pintype "passive"))
    )
    (net (code "76") (name "/DRAM_SDQS3_N") (class "Default")
      (node (ref "IC5") (pin "A2") (pinfunction "DRAM_SDQS3_N_A2") (pintype "passive"))
    )
    (net (code "77") (name "/DRAM_SDQS3_P") (class "Default")
      (node (ref "IC4") (pin "G3") (pinfunction "LDQS#_G3") (pintype "passive"))
      (node (ref "IC5") (pin "A3") (pinfunction "DRAM_SDQS3_P_A3") (pintype "passive"))
    )
    (net (code "78") (name "/DRAM_SDWE_B") (class "Default")
      (node (ref "IC16") (pin "L3") (pinfunction "WE#_L3") (pintype "passive"))
      (node (ref "IC4") (pin "L3") (pinfunction "WE#_L3") (pintype "passive"))
      (node (ref "IC5") (pin "K3") (pinfunction "DRAM_SDWE_K3") (pintype "passive"))
    )
    (net (code "79") (name "/DRAM_VREF") (class "Default")
      (node (ref "C143") (pin "2") (pinfunction "2_2") (pintype "passive"))
      (node (ref "C145") (pin "2") (pinfunction "2_2") (pintype "passive"))
      (node (ref "C146") (pin "2") (pinfunction "2_2") (pintype "passive"))
      (node (ref "C169") (pin "2") (pinfunction "2_2") (pintype "passive"))
      (node (ref "C170") (pin "2") (pinfunction "2_2") (pintype "passive"))
      (node (ref "IC16") (pin "H1") (pinfunction "VREFDQ_H1") (pintype "passive"))
      (node (ref "IC16") (pin "M8") (pinfunction "VREFCA_M8") (pintype "passive"))
      (node (ref "IC4") (pin "H1") (pinfunction "VREFDQ_H1") (pintype "passive"))
      (node (ref "IC4") (pin "M8") (pinfunction "VREFCA_M8") (pintype "passive"))
      (node (ref "IC5") (pin "M3") (pinfunction "DRAM_VREF_M3") (pintype "passive"))
    )
    (net (code "80") (name "/DRAM_ZQ0") (class "Default")
      (node (ref "IC16") (pin "L8") (pinfunction "ZQ_L8") (pintype "passive"))
      (node (ref "R65") (pin "2") (pinfunction "2_2") (pintype "passive"))
    )
    (net (code "81") (name "/DRAM_ZQ1") (class "Default")
      (node (ref "IC4") (pin "L8") (pinfunction "ZQ_L8") (pintype "passive"))
      (node (ref "R66") (pin "2") (pinfunction "2_2") (pintype "passive"))
    )
    (net (code "82") (name "/NVCC_DRAM_2V5") (class "Default")
      (node (ref "C144") (pin "2") (pinfunction "2_2") (pintype "passive"))
      (node (ref "IC5") (pin "M6") (pinfunction "NVCC_DRAM_2P5_M6") (pintype "passive"))
      (node (ref "R61") (pin "1") (pinfunction "1_1") (pintype "passive"))
    )
    (net (code "83") (name "/VDD_HIGH_CAP") (class "Default")
      (node (ref "R61") (pin "2") (pinfunction "2_2") (pintype "passive"))
    )
    (net (code "86") (name "GND") (class "Default")
      (node (ref "C136") (pin "1") (pinfunction "1_1") (pintype "passive"))
      (node (ref "C137") (pin "1") (pinfunction "1_1") (pintype "passive"))
      (node (ref "C138") (pin "1") (pinfunction "1_1") (pintype "passive"))
      (node (ref "C139") (pin "1") (pinfunction "1_1") (pintype "passive"))
      (node (ref "C140") (pin "1") (pinfunction "1_1") (pintype "passive"))
      (node (ref "C141") (pin "1") (pinfunction "1_1") (pintype "passive"))
      (node (ref "C142") (pin "1") (pinfunction "1_1") (pintype "passive"))
      (node (ref "C143") (pin "1") (pinfunction "1_1") (pintype "passive"))
      (node (ref "C144") (pin "1") (pinfunction "1_1") (pintype "passive"))
      (node (ref "C145") (pin "1") (pinfunction "1_1") (pintype "passive"))
      (node (ref "C146") (pin "1") (pinfunction "1_1") (pintype "passive"))
      (node (ref "C147") (pin "1") (pinfunction "1_1") (pintype "passive"))
      (node (ref "C148") (pin "1") (pinfunction "1_1") (pintype "passive"))
      (node (ref "C149") (pin "1") (pinfunction "1_1") (pintype "passive"))
      (node (ref "C150") (pin "1") (pinfunction "1_1") (pintype "passive"))
      (node (ref "C151") (pin "1") (pinfunction "1_1") (pintype "passive"))
      (node (ref "C152") (pin "1") (pinfunction "1_1") (pintype "passive"))
      (node (ref "C153") (pin "1") (pinfunction "1_1") (pintype "passive"))
      (node (ref "C154") (pin "1") (pinfunction "1_1") (pintype "passive"))
      (node (ref "C155") (pin "1") (pinfunction "1_1") (pintype "passive"))
      (node (ref "C156") (pin "1") (pinfunction "1_1") (pintype "passive"))
      (node (ref "C157") (pin "1") (pinfunction "1_1") (pintype "passive"))
      (node (ref "C158") (pin "1") (pinfunction "1_1") (pintype "passive"))
      (node (ref "C159") (pin "1") (pinfunction "1_1") (pintype "passive"))
      (node (ref "C160") (pin "1") (pinfunction "1_1") (pintype "passive"))
      (node (ref "C161") (pin "1") (pinfunction "1_1") (pintype "passive"))
      (node (ref "C162") (pin "1") (pinfunction "1_1") (pintype "passive"))
      (node (ref "C163") (pin "1") (pinfunction "1_1") (pintype "passive"))
      (node (ref "C164") (pin "1") (pinfunction "1_1") (pintype "passive"))
      (node (ref "C165") (pin "1") (pinfunction "1_1") (pintype "passive"))
      (node (ref "C166") (pin "1") (pinfunction "1_1") (pintype "passive"))
      (node (ref "C167") (pin "1") (pinfunction "1_1") (pintype "passive"))
      (node (ref "C168") (pin "1") (pinfunction "1_1") (pintype "passive"))
      (node (ref "C169") (pin "1") (pinfunction "1_1") (pintype "passive"))
      (node (ref "C170") (pin "1") (pinfunction "1_1") (pintype "passive"))
      (node (ref "IC16") (pin "A9") (pinfunction "VSS1_A9") (pintype "passive"))
      (node (ref "IC16") (pin "B1") (pinfunction "VSSQ1_B1") (pintype "passive"))
      (node (ref "IC16") (pin "B3") (pinfunction "VSS2_B3") (pintype "passive"))
      (node (ref "IC16") (pin "B9") (pinfunction "VSSQ2_B9") (pintype "passive"))
      (node (ref "IC16") (pin "D1") (pinfunction "VSSQ3_D1") (pintype "passive"))
      (node (ref "IC16") (pin "D8") (pinfunction "VSSQ4_D8") (pintype "passive"))
      (node (ref "IC16") (pin "E1") (pinfunction "VSS3_E1") (pintype "passive"))
      (node (ref "IC16") (pin "E2") (pinfunction "VSSQ5_E2") (pintype "passive"))
      (node (ref "IC16") (pin "E8") (pinfunction "VSSQ6_E8") (pintype "passive"))
      (node (ref "IC16") (pin "F9") (pinfunction "VSSQ7_F9") (pintype "passive"))
      (node (ref "IC16") (pin "G1") (pinfunction "VSSQ8_G1") (pintype "passive"))
      (node (ref "IC16") (pin "G8") (pinfunction "VSS4_G8") (pintype "passive"))
      (node (ref "IC16") (pin "G9") (pinfunction "VSSQ9_G9") (pintype "passive"))
      (node (ref "IC16") (pin "J2") (pinfunction "VSS5_J2") (pintype "passive"))
      (node (ref "IC16") (pin "J8") (pinfunction "VSS6_J8") (pintype "passive"))
      (node (ref "IC16") (pin "M1") (pinfunction "VSS7_M1") (pintype "passive"))
      (node (ref "IC16") (pin "M9") (pinfunction "VSS8_M9") (pintype "passive"))
      (node (ref "IC16") (pin "P1") (pinfunction "VSS9_P1") (pintype "passive"))
      (node (ref "IC16") (pin "P9") (pinfunction "VSS10_P9") (pintype "passive"))
      (node (ref "IC16") (pin "T1") (pinfunction "VSS11_T1") (pintype "passive"))
      (node (ref "IC16") (pin "T9") (pinfunction "VSS12_T9") (pintype "passive"))
      (node (ref "IC4") (pin "A9") (pinfunction "VSS1_A9") (pintype "passive"))
      (node (ref "IC4") (pin "B1") (pinfunction "VSSQ1_B1") (pintype "passive"))
      (node (ref "IC4") (pin "B3") (pinfunction "VSS2_B3") (pintype "passive"))
      (node (ref "IC4") (pin "B9") (pinfunction "VSSQ2_B9") (pintype "passive"))
      (node (ref "IC4") (pin "D1") (pinfunction "VSSQ3_D1") (pintype "passive"))
      (node (ref "IC4") (pin "D8") (pinfunction "VSSQ4_D8") (pintype "passive"))
      (node (ref "IC4") (pin "E1") (pinfunction "VSS3_E1") (pintype "passive"))
      (node (ref "IC4") (pin "E2") (pinfunction "VSSQ5_E2") (pintype "passive"))
      (node (ref "IC4") (pin "E8") (pinfunction "VSSQ6_E8") (pintype "passive"))
      (node (ref "IC4") (pin "F9") (pinfunction "VSSQ7_F9") (pintype "passive"))
      (node (ref "IC4") (pin "G1") (pinfunction "VSSQ8_G1") (pintype "passive"))
      (node (ref "IC4") (pin "G8") (pinfunction "VSS4_G8") (pintype "passive"))
      (node (ref "IC4") (pin "G9") (pinfunction "VSSQ9_G9") (pintype "passive"))
      (node (ref "IC4") (pin "J2") (pinfunction "VSS5_J2") (pintype "passive"))
      (node (ref "IC4") (pin "J8") (pinfunction "VSS6_J8") (pintype "passive"))
      (node (ref "IC4") (pin "M1") (pinfunction "VSS7_M1") (pintype "passive"))
      (node (ref "IC4") (pin "M9") (pinfunction "VSS8_M9") (pintype "passive"))
      (node (ref "IC4") (pin "P1") (pinfunction "VSS9_P1") (pintype "passive"))
      (node (ref "IC4") (pin "P9") (pinfunction "VSS10_P9") (pintype "passive"))
      (node (ref "IC4") (pin "T1") (pinfunction "VSS11_T1") (pintype "passive"))
      (node (ref "IC4") (pin "T9") (pinfunction "VSS12_T9") (pintype "passive"))
      (node (ref "R60") (pin "1") (pinfunction "1_1") (pintype "passive"))
      (node (ref "R62") (pin "2") (pinfunction "2_2") (pintype "passive"))
      (node (ref "R63") (pin "2") (pinfunction "2_2") (pintype "passive"))
      (node (ref "R64") (pin "2") (pinfunction "2_2") (pintype "passive"))
      (node (ref "R65") (pin "1") (pinfunction "1_1") (pintype "passive"))
      (node (ref "R66") (pin "1") (pinfunction "1_1") (pintype "passive"))
    )
    (net (code "87") (name "Net-(IC5-NVCC_ZQPAD)") (class "Default")
      (node (ref "IC5") (pin "C4") (pinfunction "NVCC_ZQPAD_C4") (pintype "passive"))
      (node (ref "R60") (pin "2") (pinfunction "2_2") (pintype "passive"))
    )
    (net (code "88") (name "unconnected-(IC4-NC1-PadJ1)") (class "Default")
      (node (ref "IC4") (pin "J1") (pinfunction "NC1_J1") (pintype "passive+no_connect"))
    )
    (net (code "89") (name "unconnected-(IC4-NC2-PadJ9)") (class "Default")
      (node (ref "IC4") (pin "J9") (pinfunction "NC2_J9") (pintype "passive+no_connect"))
    )
    (net (code "90") (name "unconnected-(IC4-NC3-PadL1)") (class "Default")
      (node (ref "IC4") (pin "L1") (pinfunction "NC3_L1") (pintype "passive+no_connect"))
    )
    (net (code "91") (name "unconnected-(IC4-NC4-PadL9)") (class "Default")
      (node (ref "IC4") (pin "L9") (pinfunction "NC4_L9") (pintype "passive+no_connect"))
    )
    (net (code "92") (name "unconnected-(IC4-NC5-PadM7)") (class "Default")
      (node (ref "IC4") (pin "M7") (pinfunction "NC5_M7") (pintype "passive+no_connect"))
    )
    (net (code "93") (name "unconnected-(IC16-NC1-PadJ1)") (class "Default")
      (node (ref "IC16") (pin "J1") (pinfunction "NC1_J1") (pintype "passive+no_connect"))
    )
    (net (code "94") (name "unconnected-(IC16-NC2-PadJ9)") (class "Default")
      (node (ref "IC16") (pin "J9") (pinfunction "NC2_J9") (pintype "passive+no_connect"))
    )
    (net (code "95") (name "unconnected-(IC16-NC3-PadL1)") (class "Default")
      (node (ref "IC16") (pin "L1") (pinfunction "NC3_L1") (pintype "passive+no_connect"))
    )
    (net (code "96") (name "unconnected-(IC16-NC4-PadL9)") (class "Default")
      (node (ref "IC16") (pin "L9") (pinfunction "NC4_L9") (pintype "passive+no_connect"))
    )
    (net (code "97") (name "unconnected-(IC16-NC5-PadM7)") (class "Default")
      (node (ref "IC16") (pin "M7") (pinfunction "NC5_M7") (pintype "passive+no_connect"))
    )
  )
)
